# Nusbio1_0_WaveShare_I2C_LCD.net
KiCad netlist of a schematic drawn in EAGLE
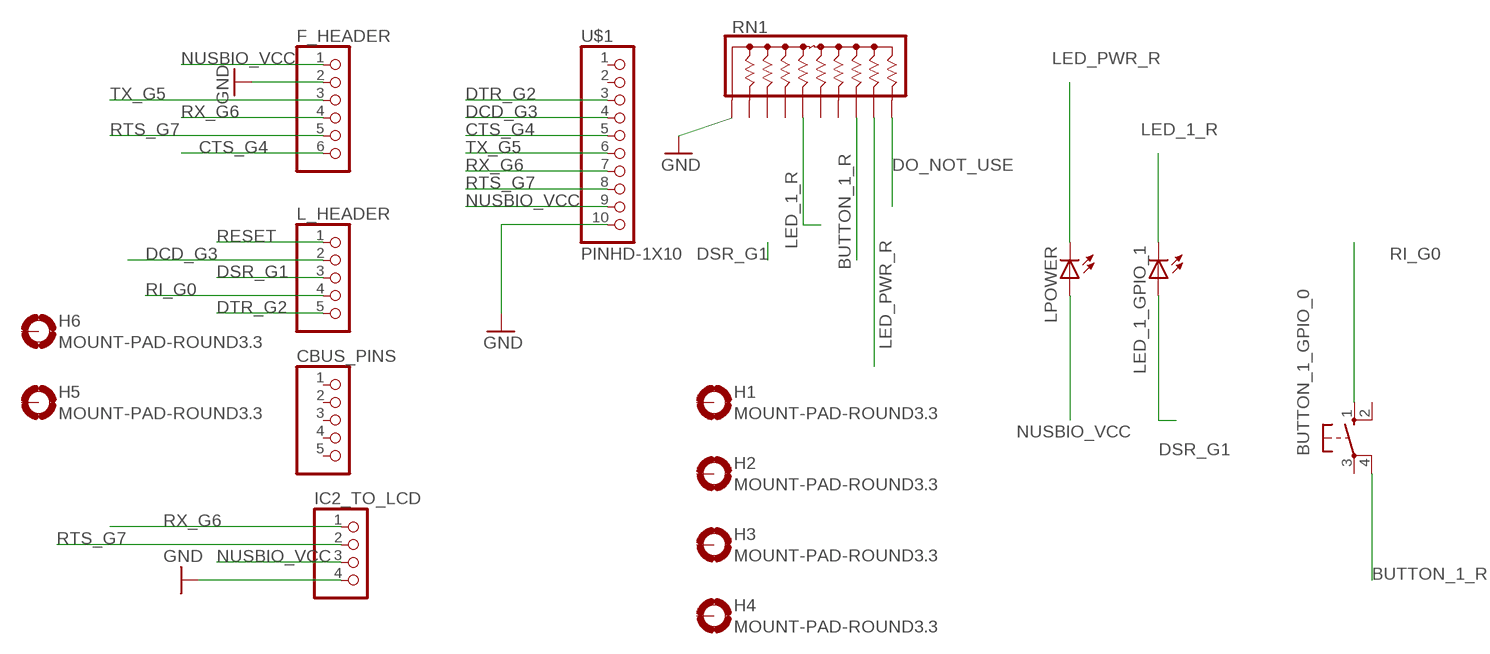
[diagram p0: schematic, sheet 1]

(export (version "E")
  (design (tool "Eeschema 10.0.6"))
  (components
    (comp (ref "BUTTON_1_GPIO_0")
      (value "10-XX")
      (footprint "eagle-import:B3F-10XX")
      (fields (field (name "MPN") "B3F-1000"))
      (libsource (lib "eagle-import") (part "10-XX"))
    )
    (comp (ref "CBUS_PINS")
      (value "PINHD-1X5")
      (footprint "eagle-import:1X05")
      (libsource (lib "eagle-import") (part "PINHD-1X5"))
    )
    (comp (ref "F_HEADER")
      (value "PINHD-1X6")
      (footprint "eagle-import:1X06")
      (libsource (lib "eagle-import") (part "PINHD-1X6"))
    )
    (comp (ref "H1")
      (value "MOUNT-PAD-ROUND3.3")
      (footprint "eagle-import:3,3-PAD")
      (libsource (lib "eagle-import") (part "MOUNT-PAD-ROUND3.3"))
    )
    (comp (ref "H2")
      (value "MOUNT-PAD-ROUND3.3")
      (footprint "eagle-import:3,3-PAD")
      (libsource (lib "eagle-import") (part "MOUNT-PAD-ROUND3.3"))
    )
    (comp (ref "H3")
      (value "MOUNT-PAD-ROUND3.3")
      (footprint "eagle-import:3,3-PAD")
      (libsource (lib "eagle-import") (part "MOUNT-PAD-ROUND3.3"))
    )
    (comp (ref "H4")
      (value "MOUNT-PAD-ROUND3.3")
      (footprint "eagle-import:3,3-PAD")
      (libsource (lib "eagle-import") (part "MOUNT-PAD-ROUND3.3"))
    )
    (comp (ref "H5")
      (value "MOUNT-PAD-ROUND3.3")
      (footprint "eagle-import:3,3-PAD")
      (libsource (lib "eagle-import") (part "MOUNT-PAD-ROUND3.3"))
    )
    (comp (ref "H6")
      (value "MOUNT-PAD-ROUND3.3")
      (footprint "eagle-import:3,3-PAD")
      (libsource (lib "eagle-import") (part "MOUNT-PAD-ROUND3.3"))
    )
    (comp (ref "IC2_TO_LCD")
      (value "PINHD-1X4")
      (footprint "eagle-import:1X04")
      (libsource (lib "eagle-import") (part "PINHD-1X4"))
    )
    (comp (ref "LED_1_GPIO_1")
      (value "LEDSMT1206")
      (footprint "eagle-import:1206")
      (libsource (lib "eagle-import") (part "LEDSMT1206"))
    )
    (comp (ref "LPOWER")
      (value "LEDSMT1206")
      (footprint "eagle-import:1206")
      (libsource (lib "eagle-import") (part "LEDSMT1206"))
    )
    (comp (ref "L_HEADER")
      (value "PINHD-1X5")
      (footprint "eagle-import:1X05")
      (libsource (lib "eagle-import") (part "PINHD-1X5"))
    )
    (comp (ref "RN1")
      (value "4610X")
      (footprint "eagle-import:SIP10")
      (libsource (lib "eagle-import") (part "4610X"))
    )
    (comp (ref "U$1")
      (value "PINHD-1X10")
      (footprint "eagle-import:1X10-BIG")
      (libsource (lib "eagle-import") (part "PINHD-1X10"))
    )
  )
  (nets
    (net (code "1") (name "/BUTTON_1_R") (class "Default")
      (node (ref "BUTTON_1_GPIO_0") (pin "4") (pinfunction "P1_4") (pintype "passive"))
      (node (ref "RN1") (pin "8") (pinfunction "8_8") (pintype "passive"))
    )
    (net (code "2") (name "/CTS_G4") (class "Default")
      (node (ref "F_HEADER") (pin "6") (pinfunction "6_6") (pintype "passive"))
      (node (ref "U$1") (pin "5") (pinfunction "5_5") (pintype "passive"))
    )
    (net (code "3") (name "/DCD_G3") (class "Default")
      (node (ref "L_HEADER") (pin "2") (pinfunction "2_2") (pintype "passive"))
      (node (ref "U$1") (pin "4") (pinfunction "4_4") (pintype "passive"))
    )
    (net (code "4") (name "/DO_NOT_USE") (class "Default")
      (node (ref "RN1") (pin "10") (pinfunction "10_10") (pintype "passive"))
    )
    (net (code "5") (name "/DSR_G1") (class "Default")
      (node (ref "LED_1_GPIO_1") (pin "A") (pinfunction "A_A") (pintype "passive"))
      (node (ref "L_HEADER") (pin "3") (pinfunction "3_3") (pintype "passive"))
    )
    (net (code "6") (name "/DTR_G2") (class "Default")
      (node (ref "L_HEADER") (pin "5") (pinfunction "5_5") (pintype "passive"))
      (node (ref "U$1") (pin "3") (pinfunction "3_3") (pintype "passive"))
    )
    (net (code "7") (name "/LED_1_R") (class "Default")
      (node (ref "LED_1_GPIO_1") (pin "C") (pinfunction "C_C") (pintype "passive"))
      (node (ref "RN1") (pin "5") (pinfunction "5_5") (pintype "passive"))
    )
    (net (code "8") (name "/LED_PWR_R") (class "Default")
      (node (ref "LPOWER") (pin "C") (pinfunction "C_C") (pintype "passive"))
      (node (ref "RN1") (pin "9") (pinfunction "9_9") (pintype "passive"))
    )
    (net (code "9") (name "/NUSBIO_VCC") (class "Default")
      (node (ref "F_HEADER") (pin "1") (pinfunction "1_1") (pintype "passive"))
      (node (ref "IC2_TO_LCD") (pin "3") (pinfunction "3_3") (pintype "passive"))
      (node (ref "LPOWER") (pin "A") (pinfunction "A_A") (pintype "passive"))
      (node (ref "U$1") (pin "9") (pinfunction "9_9") (pintype "passive"))
    )
    (net (code "10") (name "/RESET") (class "Default")
      (node (ref "L_HEADER") (pin "1") (pinfunction "1_1") (pintype "passive"))
    )
    (net (code "11") (name "/RI_G0") (class "Default")
      (node (ref "BUTTON_1_GPIO_0") (pin "1") (pinfunction "S_1") (pintype "passive"))
      (node (ref "L_HEADER") (pin "4") (pinfunction "4_4") (pintype "passive"))
    )
    (net (code "12") (name "/RTS_G7") (class "Default")
      (node (ref "F_HEADER") (pin "5") (pinfunction "5_5") (pintype "passive"))
      (node (ref "IC2_TO_LCD") (pin "2") (pinfunction "2_2") (pintype "passive"))
      (node (ref "U$1") (pin "8") (pinfunction "8_8") (pintype "passive"))
    )
    (net (code "13") (name "/RX_G6") (class "Default")
      (node (ref "F_HEADER") (pin "4") (pinfunction "4_4") (pintype "passive"))
      (node (ref "IC2_TO_LCD") (pin "1") (pinfunction "1_1") (pintype "passive"))
      (node (ref "U$1") (pin "7") (pinfunction "7_7") (pintype "passive"))
    )
    (net (code "14") (name "/TX_G5") (class "Default")
      (node (ref "F_HEADER") (pin "3") (pinfunction "3_3") (pintype "passive"))
      (node (ref "U$1") (pin "6") (pinfunction "6_6") (pintype "passive"))
    )
    (net (code "15") (name "GND") (class "Default")
      (node (ref "F_HEADER") (pin "2") (pinfunction "2_2") (pintype "passive"))
      (node (ref "IC2_TO_LCD") (pin "4") (pinfunction "4_4") (pintype "passive"))
      (node (ref "RN1") (pin "1") (pinfunction "1_1") (pintype "passive"))
      (node (ref "U$1") (pin "10") (pinfunction "10_10") (pintype "passive"))
    )
    (net (code "16") (name "unconnected-(BUTTON_1_GPIO_0-P-Pad3)") (class "Default")
      (node (ref "BUTTON_1_GPIO_0") (pin "3") (pinfunction "P_3") (pintype "passive"))
    )
    (net (code "17") (name "unconnected-(BUTTON_1_GPIO_0-S1-Pad2)") (class "Default")
      (node (ref "BUTTON_1_GPIO_0") (pin "2") (pinfunction "S1_2") (pintype "passive"))
    )
    (net (code "18") (name "unconnected-(CBUS_PINS-Pad1)") (class "Default")
      (node (ref "CBUS_PINS") (pin "1") (pinfunction "1_1") (pintype "passive"))
    )
    (net (code "19") (name "unconnected-(CBUS_PINS-Pad2)") (class "Default")
      (node (ref "CBUS_PINS") (pin "2") (pinfunction "2_2") (pintype "passive"))
    )
    (net (code "20") (name "unconnected-(CBUS_PINS-Pad3)") (class "Default")
      (node (ref "CBUS_PINS") (pin "3") (pinfunction "3_3") (pintype "passive"))
    )
    (net (code "21") (name "unconnected-(CBUS_PINS-Pad4)") (class "Default")
      (node (ref "CBUS_PINS") (pin "4") (pinfunction "4_4") (pintype "passive"))
    )
    (net (code "22") (name "unconnected-(CBUS_PINS-Pad5)") (class "Default")
      (node (ref "CBUS_PINS") (pin "5") (pinfunction "5_5") (pintype "passive"))
    )
    (net (code "23") (name "unconnected-(H1-MOUNT-PadB3,3)") (class "Default")
      (node (ref "H1") (pin "B3,3") (pinfunction "MOUNT_B3,3") (pintype "passive"))
    )
    (net (code "24") (name "unconnected-(H2-MOUNT-PadB3,3)") (class "Default")
      (node (ref "H2") (pin "B3,3") (pinfunction "MOUNT_B3,3") (pintype "passive"))
    )
    (net (code "25") (name "unconnected-(H3-MOUNT-PadB3,3)") (class "Default")
      (node (ref "H3") (pin "B3,3") (pinfunction "MOUNT_B3,3") (pintype "passive"))
    )
    (net (code "26") (name "unconnected-(H4-MOUNT-PadB3,3)") (class "Default")
      (node (ref "H4") (pin "B3,3") (pinfunction "MOUNT_B3,3") (pintype "passive"))
    )
    (net (code "27") (name "unconnected-(H5-MOUNT-PadB3,3)") (class "Default")
      (node (ref "H5") (pin "B3,3") (pinfunction "MOUNT_B3,3") (pintype "passive"))
    )
    (net (code "28") (name "unconnected-(H6-MOUNT-PadB3,3)") (class "Default")
      (node (ref "H6") (pin "B3,3") (pinfunction "MOUNT_B3,3") (pintype "passive"))
    )
    (net (code "29") (name "unconnected-(RN1-Pad2)") (class "Default")
      (node (ref "RN1") (pin "2") (pinfunction "2_2") (pintype "passive"))
    )
    (net (code "30") (name "unconnected-(RN1-Pad3)") (class "Default")
      (node (ref "RN1") (pin "3") (pinfunction "3_3") (pintype "passive"))
    )
    (net (code "31") (name "unconnected-(RN1-Pad4)") (class "Default")
      (node (ref "RN1") (pin "4") (pinfunction "4_4") (pintype "passive"))
    )
    (net (code "32") (name "unconnected-(RN1-Pad6)") (class "Default")
      (node (ref "RN1") (pin "6") (pinfunction "6_6") (pintype "passive"))
    )
    (net (code "33") (name "unconnected-(RN1-Pad7)") (class "Default")
      (node (ref "RN1") (pin "7") (pinfunction "7_7") (pintype "passive"))
    )
    (net (code "34") (name "unconnected-(U$1-Pad1)") (class "Default")
      (node (ref "U$1") (pin "1") (pinfunction "1_1") (pintype "passive"))
    )
    (net (code "35") (name "unconnected-(U$1-Pad2)") (class "Default")
      (node (ref "U$1") (pin "2") (pinfunction "2_2") (pintype "passive"))
    )
  )
)
